# 5_-_Motor_Driver.net
KiCad netlist of a schematic drawn in Altium Designer
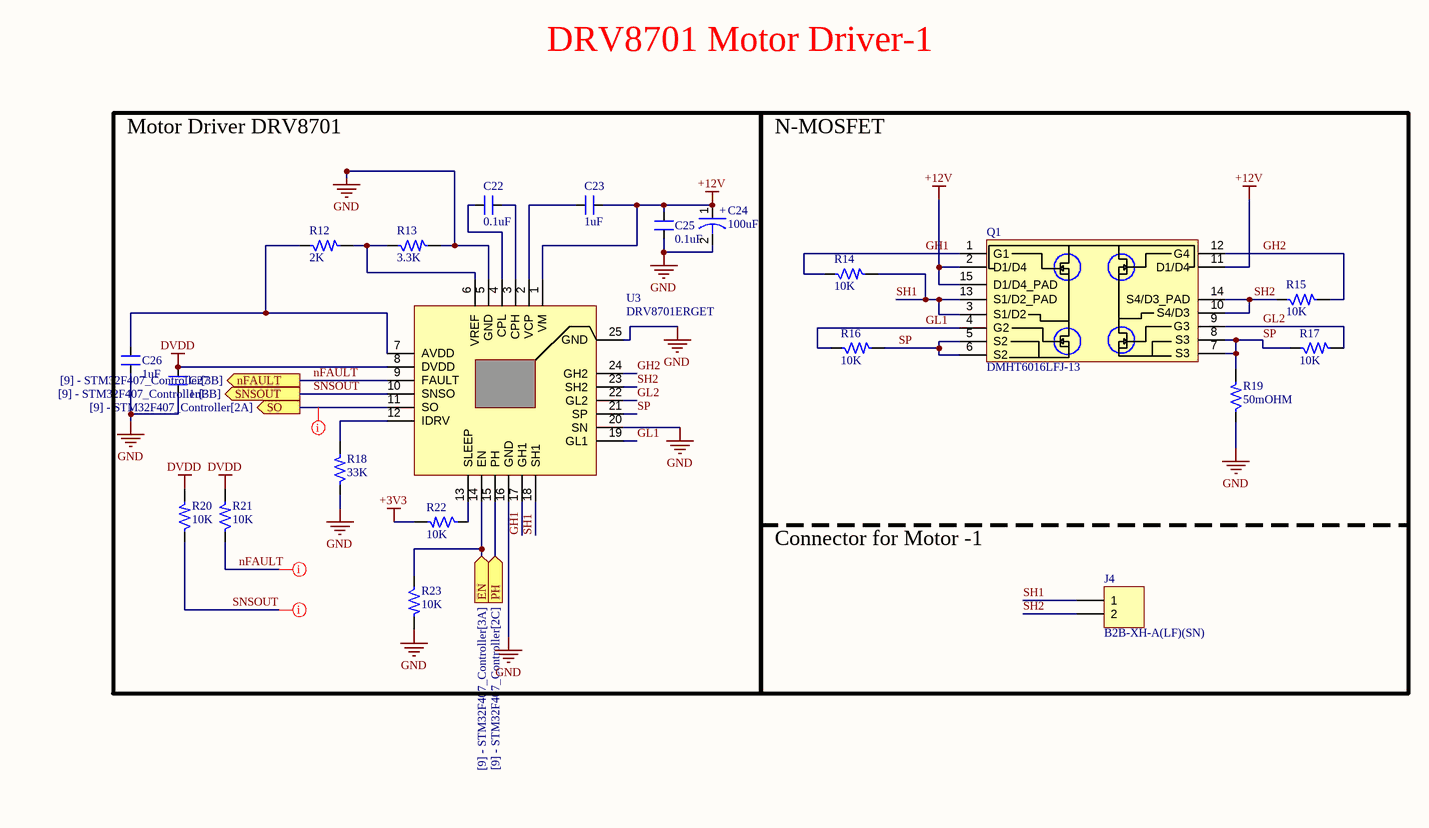
[diagram p0: [5] - Motor_Driver.SchDoc]

(export (version "E")
  (design (tool "Eeschema 10.0.6"))
  (components
    (comp (ref "C22")
      (value "0.1uF")
      (footprint "CAP_0805")
      (description "0.1µF ±10% 50V Ceramic Capacitor X7R 0805 (2012 Metric)")
      (fields
        (field (name "MANUFACTURER") "Samsung")
        (field (name "MANUFACTURER PART NUMBER") "CL21B104KBCNNNC")
      )
      (libsource (lib "ESTEEMPCBLIB") (part "CAP_0.1uF-50V-10%-0805"))
    )
    (comp (ref "C23")
      (value "1uF")
      (footprint "CAP_0805")
      (description "1µF ±5% 50V Ceramic Capacitor X7R 0805 (2012 Metric)")
      (fields
        (field (name "MANUFACTURER") "Samsung")
        (field (name "MANUFACTURER PART NUMBER") "CC0805JKX7R9BB105")
      )
      (libsource (lib "ESTEEMPCBLIB") (part "CAP_1uF-50V-5%-0805"))
    )
    (comp (ref "C24")
      (value "100uF")
      (footprint "ACAP_P236_D305_H303_RAD")
      (description "100µF 25V Aluminum Electrolytic Capacitors Radial, Can - SMD 1000 Hrs @ 105°C")
      (fields
        (field (name "MANUFACTURER") "Nichicon")
        (field (name "MANUFACTURER PART NUMBER") "UWT1E101MCL1GS")
      )
      (libsource (lib "ESTEEMPCBLIB") (part "CAP-P_100uF-25V-20%-RAD"))
    )
    (comp (ref "C25")
      (value "0.1uF")
      (footprint "CAP_0805")
      (description "0.1µF ±10% 50V Ceramic Capacitor X7R 0805 (2012 Metric)")
      (fields
        (field (name "MANUFACTURER") "Samsung")
        (field (name "MANUFACTURER PART NUMBER") "CL21B104KBCNNNC")
      )
      (libsource (lib "ESTEEMPCBLIB") (part "CAP_0.1uF-50V-10%-0805"))
    )
    (comp (ref "C26")
      (value "1uF")
      (footprint "CAP_0805")
      (description "1µF ±5% 50V Ceramic Capacitor X7R 0805 (2012 Metric)")
      (fields
        (field (name "MANUFACTURER") "Samsung")
        (field (name "MANUFACTURER PART NUMBER") "CC0805JKX7R9BB105")
      )
      (libsource (lib "ESTEEMPCBLIB") (part "CAP_1uF-50V-5%-0805"))
    )
    (comp (ref "C27")
      (value "1uF")
      (footprint "CAP_0805")
      (description "1µF ±5% 50V Ceramic Capacitor X7R 0805 (2012 Metric)")
      (fields
        (field (name "MANUFACTURER") "Samsung")
        (field (name "MANUFACTURER PART NUMBER") "CC0805JKX7R9BB105")
      )
      (libsource (lib "ESTEEMPCBLIB") (part "CAP_1uF-50V-5%-0805"))
    )
    (comp (ref "J4")
      (value "B2B-XH-A(LF)(SN)")
      (footprint "CON2_100_B2B-XH-A_TH_ST")
      (description "2 Pins, 1 Row 2.54mm Pitch, Straight Connector, male")
      (fields (field (name "MANUFACTURER") "JST") (field (name "MATING PART NUMBER") "XHP-2"))
      (libsource (lib "ESTEEMPCBLIB") (part "CON-PLG_2X1-100-ST-TH"))
    )
    (comp (ref "Q1")
      (value "DMHT6016LFJ-13")
      (footprint "DFN5045-12_33_212_27X15_SMD_1")
      (description "Mosfet Array 4 N-Channel 14.8A (Ta) Surface Mount V-DFN5045-12")
      (fields (field (name "MANUFACTURER") "ON Semiconductor"))
      (libsource (lib "ESTEEMPCBLIB") (part "MOSFET-N_60V-14.8A-V-DFN5045-12"))
    )
    (comp (ref "R12")
      (value "2K")
      (footprint "RES_0805")
      (description "2 kOhms ±1% 0.125W, 1/8W Chip Resistor 0805 (2012 Metric) Moisture Resistant Thick Film")
      (fields
        (field (name "MANUFACTURER") "TE Connectivity")
        (field (name "MANUFACTURER PART NUMBER") "RC0805FR-072KL")
      )
      (libsource (lib "ESTEEMPCBLIB") (part "RES_2K-0.125W-1%-0805"))
    )
    (comp (ref "R13")
      (value "3.3K")
      (footprint "RES_0805")
      (description "3.3 kOhms ±1% 0.125W, 1/8W Chip Resistor 0805 (2012 Metric) Thick Film")
      (fields (field (name "MANUFACTURER") "Panasonic") (field (name "MANUFACTURER PART NUMBER") "1623214-1"))
      (libsource (lib "ESTEEMPCBLIB") (part "RES_3.3K-0.125W-1%-0805"))
    )
    (comp (ref "R14")
      (value "10K")
      (footprint "RES_0805")
      (description "10 kOhms ±1% 0.125W, 1/8W Chip Resistor 0805 (2012 Metric) Automotive AEC-Q200 Thick Film")
      (fields (field (name "MANUFACTURER") "CTS") (field (name "MANUFACTURER PART NUMBER") "WR08X1002FTL"))
      (libsource (lib "ESTEEMPCBLIB") (part "RES_10K-0.125W-1%-0805"))
    )
    (comp (ref "R15")
      (value "10K")
      (footprint "RES_0805")
      (description "10 kOhms ±1% 0.125W, 1/8W Chip Resistor 0805 (2012 Metric) Automotive AEC-Q200 Thick Film")
      (fields (field (name "MANUFACTURER") "CTS") (field (name "MANUFACTURER PART NUMBER") "WR08X1002FTL"))
      (libsource (lib "ESTEEMPCBLIB") (part "RES_10K-0.125W-1%-0805"))
    )
    (comp (ref "R16")
      (value "10K")
      (footprint "RES_0805")
      (description "10 kOhms ±1% 0.125W, 1/8W Chip Resistor 0805 (2012 Metric) Automotive AEC-Q200 Thick Film")
      (fields (field (name "MANUFACTURER") "CTS") (field (name "MANUFACTURER PART NUMBER") "WR08X1002FTL"))
      (libsource (lib "ESTEEMPCBLIB") (part "RES_10K-0.125W-1%-0805"))
    )
    (comp (ref "R17")
      (value "10K")
      (footprint "RES_0805")
      (description "10 kOhms ±1% 0.125W, 1/8W Chip Resistor 0805 (2012 Metric) Automotive AEC-Q200 Thick Film")
      (fields (field (name "MANUFACTURER") "CTS") (field (name "MANUFACTURER PART NUMBER") "WR08X1002FTL"))
      (libsource (lib "ESTEEMPCBLIB") (part "RES_10K-0.125W-1%-0805"))
    )
    (comp (ref "R18")
      (value "33K")
      (footprint "RES_0805")
      (fields
        (field (name "MANUFACTURER") "Vishay BCcomponents")
        (field (name "MANUFACTURER PART NUMBER") "CRG0805F33K")
      )
      (libsource (lib "ESTEEMPCBLIB") (part "RES_33K-0.125W-1%-0805"))
    )
    (comp (ref "R19")
      (value "50mOHM")
      (footprint "RES_2512")
      (fields
        (field (name "MANUFACTURER") "Yageo")
        (field (name "MANUFACTURER PART NUMBER") "PA2512FKF7W0R05E")
      )
      (libsource (lib "ESTEEMPCBLIB") (part "RES_50mOhm-2W-1%-2512"))
    )
    (comp (ref "R20")
      (value "10K")
      (footprint "RES_0805")
      (description "10 kOhms ±1% 0.125W, 1/8W Chip Resistor 0805 (2012 Metric) Automotive AEC-Q200 Thick Film")
      (fields (field (name "MANUFACTURER") "CTS") (field (name "MANUFACTURER PART NUMBER") "WR08X1002FTL"))
      (libsource (lib "ESTEEMPCBLIB") (part "RES_10K-0.125W-1%-0805"))
    )
    (comp (ref "R21")
      (value "10K")
      (footprint "RES_0805")
      (description "10 kOhms ±1% 0.125W, 1/8W Chip Resistor 0805 (2012 Metric) Automotive AEC-Q200 Thick Film")
      (fields (field (name "MANUFACTURER") "CTS") (field (name "MANUFACTURER PART NUMBER") "WR08X1002FTL"))
      (libsource (lib "ESTEEMPCBLIB") (part "RES_10K-0.125W-1%-0805"))
    )
    (comp (ref "R22")
      (value "10K")
      (footprint "RES_0805")
      (description "10 kOhms ±1% 0.125W, 1/8W Chip Resistor 0805 (2012 Metric) Automotive AEC-Q200 Thick Film")
      (fields (field (name "MANUFACTURER") "CTS") (field (name "MANUFACTURER PART NUMBER") "WR08X1002FTL"))
      (libsource (lib "ESTEEMPCBLIB") (part "RES_10K-0.125W-1%-0805"))
    )
    (comp (ref "R23")
      (value "10K")
      (footprint "RES_0805")
      (description "10 kOhms ±1% 0.125W, 1/8W Chip Resistor 0805 (2012 Metric) Automotive AEC-Q200 Thick Film")
      (fields (field (name "MANUFACTURER") "CTS") (field (name "MANUFACTURER PART NUMBER") "WR08X1002FTL"))
      (libsource (lib "ESTEEMPCBLIB") (part "RES_10K-0.125W-1%-0805"))
    )
    (comp (ref "U3")
      (value "DRV8701ERGET")
      (footprint "VFQFN24_19.6_196_12X32_SMD_1")
      (description "Motor Driver Power MOSFET Parallel 24-VQFN (4x4)")
      (fields (field (name "MANUFACTURER") "Texas Instruments"))
      (libsource (lib "ESTEEMPCBLIB") (part "IC_DRV8701ERGET"))
    )
  )
  (nets
    (net (code "1") (name "+3V3") (class "Default")
      (node (ref "R22") (pin "2") (pinfunction "2_2") (pintype "passive"))
    )
    (net (code "2") (name "+12V") (class "Default")
      (node (ref "C23") (pin "2") (pinfunction "2_2") (pintype "passive"))
      (node (ref "C24") (pin "1") (pinfunction "1_1") (pintype "passive"))
      (node (ref "C25") (pin "2") (pinfunction "2_2") (pintype "passive"))
      (node (ref "Q1") (pin "11") (pinfunction "D1/D4_11") (pintype "passive"))
      (node (ref "Q1") (pin "15") (pinfunction "D1/D4_PAD_15") (pintype "passive"))
      (node (ref "Q1") (pin "2") (pinfunction "D1/D4_2") (pintype "passive"))
      (node (ref "U3") (pin "1") (pinfunction "VM_1") (pintype "passive"))
    )
    (net (code "3") (name "/EN") (class "Default")
      (node (ref "R23") (pin "1") (pinfunction "1_1") (pintype "passive"))
      (node (ref "U3") (pin "14") (pinfunction "EN_14") (pintype "passive"))
    )
    (net (code "4") (name "/GH1") (class "Default")
      (node (ref "Q1") (pin "1") (pinfunction "G1_1") (pintype "passive"))
      (node (ref "R14") (pin "1") (pinfunction "1_1") (pintype "passive"))
      (node (ref "U3") (pin "17") (pinfunction "GH1_17") (pintype "passive"))
    )
    (net (code "5") (name "/GH2") (class "Default")
      (node (ref "Q1") (pin "12") (pinfunction "G4_12") (pintype "passive"))
      (node (ref "R15") (pin "2") (pinfunction "2_2") (pintype "passive"))
      (node (ref "U3") (pin "24") (pinfunction "GH2_24") (pintype "passive"))
    )
    (net (code "6") (name "/GL1") (class "Default")
      (node (ref "Q1") (pin "4") (pinfunction "G2_4") (pintype "passive"))
      (node (ref "R16") (pin "1") (pinfunction "1_1") (pintype "passive"))
      (node (ref "U3") (pin "19") (pinfunction "GL1_19") (pintype "passive"))
    )
    (net (code "7") (name "/GL2") (class "Default")
      (node (ref "Q1") (pin "9") (pinfunction "G3_9") (pintype "passive"))
      (node (ref "R17") (pin "2") (pinfunction "2_2") (pintype "passive"))
      (node (ref "U3") (pin "22") (pinfunction "GL2_22") (pintype "passive"))
    )
    (net (code "8") (name "/PH") (class "Default")
      (node (ref "U3") (pin "15") (pinfunction "PH_15") (pintype "passive"))
    )
    (net (code "9") (name "/SH1") (class "Default")
      (node (ref "J4") (pin "1") (pinfunction "1_1") (pintype "passive"))
      (node (ref "Q1") (pin "13") (pinfunction "S1/D2_PAD_13") (pintype "passive"))
      (node (ref "Q1") (pin "3") (pinfunction "S1/D2_3") (pintype "passive"))
      (node (ref "R14") (pin "2") (pinfunction "2_2") (pintype "passive"))
      (node (ref "U3") (pin "18") (pinfunction "SH1_18") (pintype "passive"))
    )
    (net (code "10") (name "/SH2") (class "Default")
      (node (ref "J4") (pin "2") (pinfunction "2_2") (pintype "passive"))
      (node (ref "Q1") (pin "10") (pinfunction "S4/D3_10") (pintype "passive"))
      (node (ref "Q1") (pin "14") (pinfunction "S4/D3_PAD_14") (pintype "passive"))
      (node (ref "R15") (pin "1") (pinfunction "1_1") (pintype "passive"))
      (node (ref "U3") (pin "23") (pinfunction "SH2_23") (pintype "passive"))
    )
    (net (code "11") (name "/SNSOUT") (class "Default")
      (node (ref "R20") (pin "1") (pinfunction "1_1") (pintype "passive"))
      (node (ref "U3") (pin "10") (pinfunction "SNSO_10") (pintype "passive"))
    )
    (net (code "12") (name "/SO") (class "Default")
      (node (ref "U3") (pin "11") (pinfunction "SO_11") (pintype "passive"))
    )
    (net (code "13") (name "/SP") (class "Default")
      (node (ref "Q1") (pin "5") (pinfunction "S2_5") (pintype "passive"))
      (node (ref "Q1") (pin "6") (pinfunction "S2_6") (pintype "passive"))
      (node (ref "Q1") (pin "7") (pinfunction "S3_7") (pintype "passive"))
      (node (ref "Q1") (pin "8") (pinfunction "S3_8") (pintype "passive"))
      (node (ref "R16") (pin "2") (pinfunction "2_2") (pintype "passive"))
      (node (ref "R17") (pin "1") (pinfunction "1_1") (pintype "passive"))
      (node (ref "R19") (pin "2") (pinfunction "2_2") (pintype "passive"))
      (node (ref "U3") (pin "21") (pinfunction "SP_21") (pintype "passive"))
    )
    (net (code "14") (name "/nFAULT") (class "Default")
      (node (ref "R21") (pin "1") (pinfunction "1_1") (pintype "passive"))
      (node (ref "U3") (pin "9") (pinfunction "FAULT_9") (pintype "passive"))
    )
    (net (code "15") (name "DVDD") (class "Default")
      (node (ref "C27") (pin "1") (pinfunction "1_1") (pintype "passive"))
      (node (ref "R20") (pin "2") (pinfunction "2_2") (pintype "passive"))
      (node (ref "R21") (pin "2") (pinfunction "2_2") (pintype "passive"))
      (node (ref "U3") (pin "8") (pinfunction "DVDD_8") (pintype "passive"))
    )
    (net (code "16") (name "GND") (class "Default")
      (node (ref "C24") (pin "2") (pinfunction "2_2") (pintype "passive"))
      (node (ref "C25") (pin "1") (pinfunction "1_1") (pintype "passive"))
      (node (ref "C26") (pin "1") (pinfunction "1_1") (pintype "passive"))
      (node (ref "C27") (pin "2") (pinfunction "2_2") (pintype "passive"))
      (node (ref "R13") (pin "2") (pinfunction "2_2") (pintype "passive"))
      (node (ref "R18") (pin "1") (pinfunction "1_1") (pintype "passive"))
      (node (ref "R19") (pin "1") (pinfunction "1_1") (pintype "passive"))
      (node (ref "R23") (pin "2") (pinfunction "2_2") (pintype "passive"))
      (node (ref "U3") (pin "16") (pinfunction "GND_16") (pintype "passive"))
      (node (ref "U3") (pin "20") (pinfunction "SN_20") (pintype "passive"))
      (node (ref "U3") (pin "25") (pinfunction "GND_25") (pintype "passive"))
      (node (ref "U3") (pin "5") (pinfunction "GND_5") (pintype "passive"))
    )
    (net (code "17") (name "Net-(U3-AVDD)") (class "Default")
      (node (ref "C26") (pin "2") (pinfunction "2_2") (pintype "passive"))
      (node (ref "R12") (pin "1") (pinfunction "1_1") (pintype "passive"))
      (node (ref "U3") (pin "7") (pinfunction "AVDD_7") (pintype "passive"))
    )
    (net (code "18") (name "Net-(U3-CPH)") (class "Default")
      (node (ref "C22") (pin "1") (pinfunction "1_1") (pintype "passive"))
      (node (ref "U3") (pin "3") (pinfunction "CPH_3") (pintype "passive"))
    )
    (net (code "19") (name "Net-(U3-CPL)") (class "Default")
      (node (ref "C22") (pin "2") (pinfunction "2_2") (pintype "passive"))
      (node (ref "U3") (pin "4") (pinfunction "CPL_4") (pintype "passive"))
    )
    (net (code "20") (name "Net-(U3-IDRV)") (class "Default")
      (node (ref "R18") (pin "2") (pinfunction "2_2") (pintype "passive"))
      (node (ref "U3") (pin "12") (pinfunction "IDRV_12") (pintype "passive"))
    )
    (net (code "21") (name "Net-(U3-SLEEP)") (class "Default")
      (node (ref "R22") (pin "1") (pinfunction "1_1") (pintype "passive"))
      (node (ref "U3") (pin "13") (pinfunction "SLEEP_13") (pintype "passive"))
    )
    (net (code "22") (name "Net-(U3-VCP)") (class "Default")
      (node (ref "C23") (pin "1") (pinfunction "1_1") (pintype "passive"))
      (node (ref "U3") (pin "2") (pinfunction "VCP_2") (pintype "passive"))
    )
    (net (code "23") (name "Net-(U3-VREF)") (class "Default")
      (node (ref "R12") (pin "2") (pinfunction "2_2") (pintype "passive"))
      (node (ref "R13") (pin "1") (pinfunction "1_1") (pintype "passive"))
      (node (ref "U3") (pin "6") (pinfunction "VREF_6") (pintype "passive"))
    )
  )
)
